# board.net
KiCad netlist of a schematic drawn in EAGLE
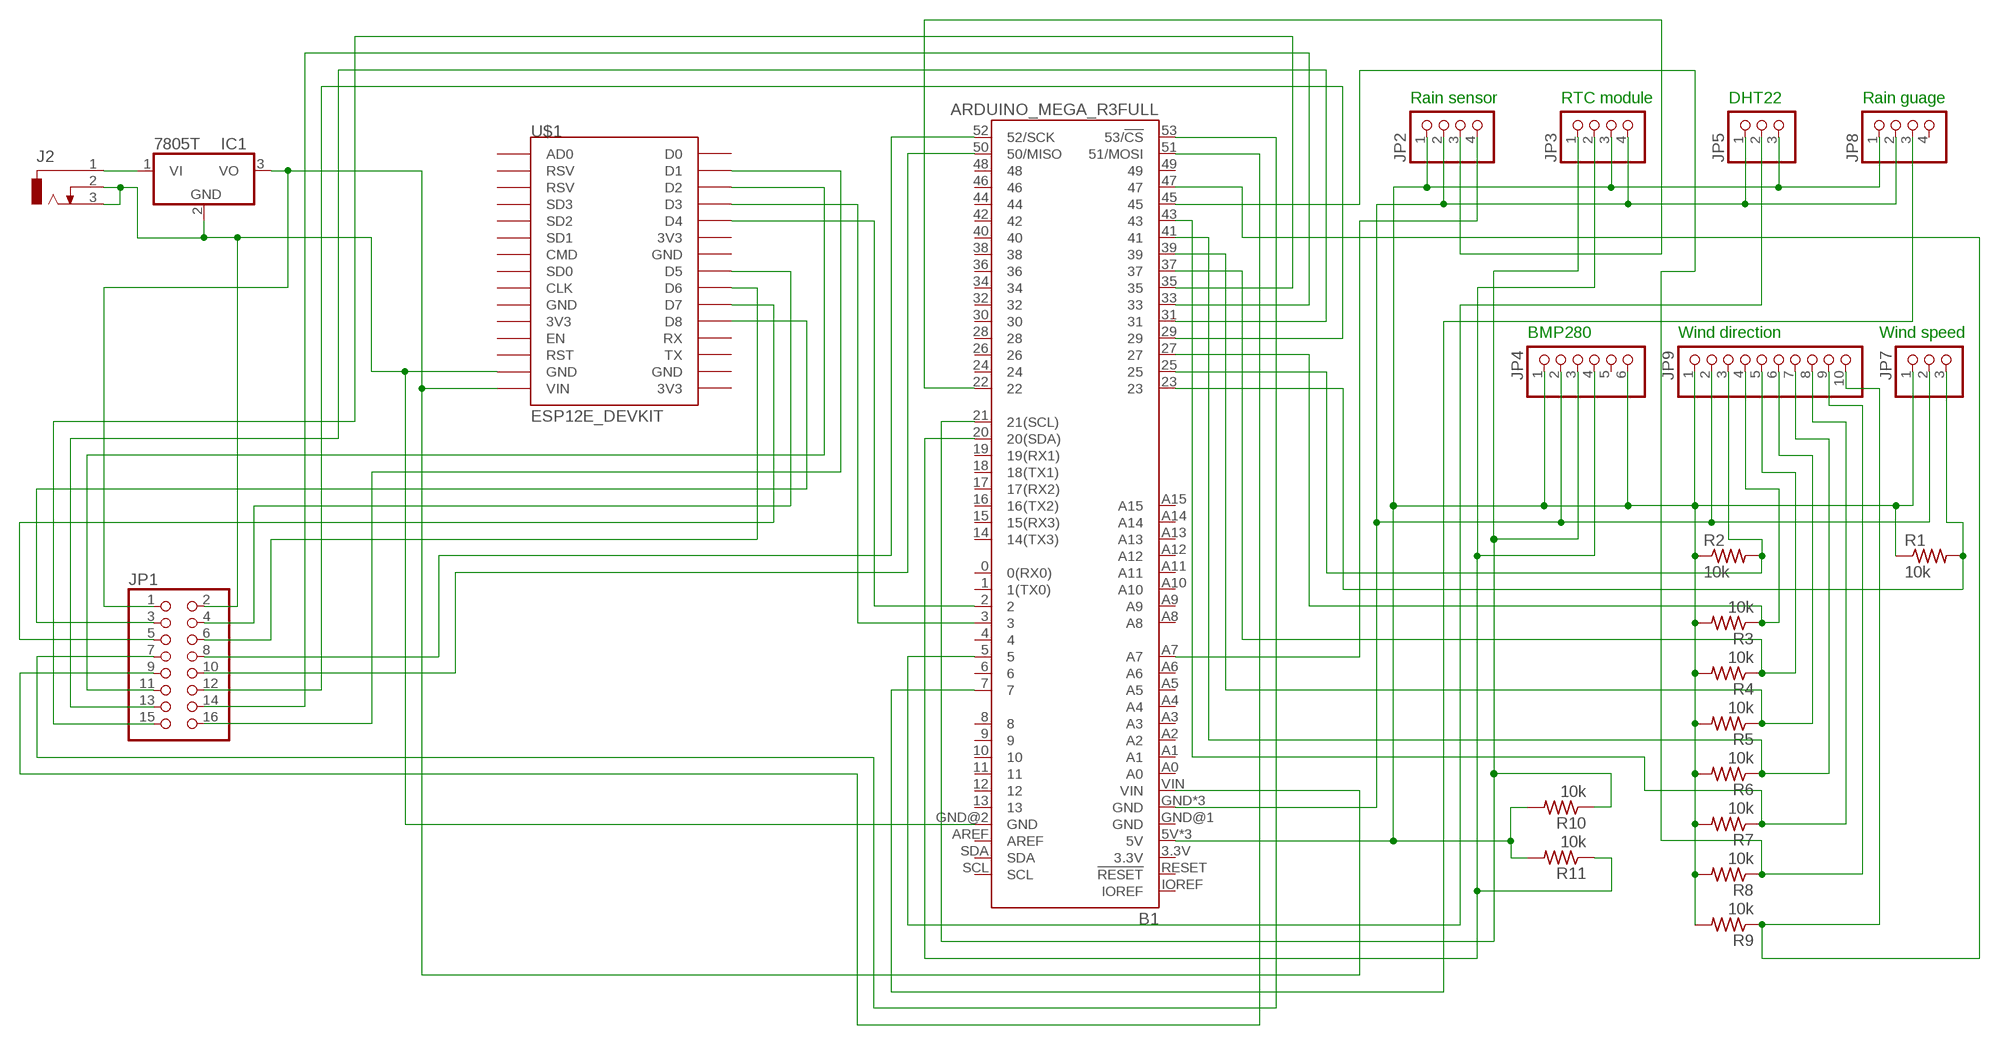
[diagram p0: schematic, sheet 1]

(export (version "E")
  (design (tool "Eeschema 10.0.6"))
  (components
    (comp (ref "B1")
      (value "ARDUINO_MEGA_R3FULL")
      (footprint "eagle-import:ARDUINO_MEGA_NO_SILK")
      (libsource (lib "eagle-import") (part "ARDUINO_MEGA_R3FULL"))
    )
    (comp (ref "IC1")
      (value "7805T")
      (footprint "eagle-import:TO220H")
      (libsource (lib "eagle-import") (part "78T05"))
    )
    (comp (ref "J2")
      (value "DCJ0303")
      (footprint "eagle-import:DCJ0303")
      (libsource (lib "eagle-import") (part "DCJ0303"))
    )
    (comp (ref "JP1")
      (value "PINHD-2X8/90")
      (footprint "eagle-import:2X08_90")
      (libsource (lib "eagle-import") (part "PINHD-2X8/90"))
    )
    (comp (ref "JP2")
      (value "PINHD-1X4")
      (footprint "eagle-import:1X04")
      (libsource (lib "eagle-import") (part "PINHD-1X4"))
    )
    (comp (ref "JP3")
      (value "PINHD-1X4")
      (footprint "eagle-import:1X04")
      (libsource (lib "eagle-import") (part "PINHD-1X4"))
    )
    (comp (ref "JP4")
      (value "PINHD-1X6")
      (footprint "eagle-import:1X06")
      (libsource (lib "eagle-import") (part "PINHD-1X6"))
    )
    (comp (ref "JP5")
      (value "PINHD-1X3")
      (footprint "eagle-import:1X03")
      (libsource (lib "eagle-import") (part "PINHD-1X3"))
    )
    (comp (ref "JP7")
      (value "PINHD-1X3")
      (footprint "eagle-import:1X03")
      (libsource (lib "eagle-import") (part "PINHD-1X3"))
    )
    (comp (ref "JP8")
      (value "PINHD-1X4")
      (footprint "eagle-import:1X04")
      (libsource (lib "eagle-import") (part "PINHD-1X4"))
    )
    (comp (ref "JP9")
      (value "PINHD-1X10")
      (footprint "eagle-import:1X10")
      (libsource (lib "eagle-import") (part "PINHD-1X10"))
    )
    (comp (ref "R1")
      (value "10k")
      (footprint "eagle-import:0207_10")
      (libsource (lib "eagle-import") (part "R-US_0207/10"))
    )
    (comp (ref "R2")
      (value "10k")
      (footprint "eagle-import:0207_10")
      (libsource (lib "eagle-import") (part "R-US_0207/10"))
    )
    (comp (ref "R3")
      (value "10k")
      (footprint "eagle-import:0207_10")
      (libsource (lib "eagle-import") (part "R-US_0207/10"))
    )
    (comp (ref "R4")
      (value "10k")
      (footprint "eagle-import:0207_10")
      (libsource (lib "eagle-import") (part "R-US_0207/10"))
    )
    (comp (ref "R5")
      (value "10k")
      (footprint "eagle-import:0207_10")
      (libsource (lib "eagle-import") (part "R-US_0207/10"))
    )
    (comp (ref "R6")
      (value "10k")
      (footprint "eagle-import:0207_10")
      (libsource (lib "eagle-import") (part "R-US_0207/10"))
    )
    (comp (ref "R7")
      (value "10k")
      (footprint "eagle-import:0207_10")
      (libsource (lib "eagle-import") (part "R-US_0207/10"))
    )
    (comp (ref "R8")
      (value "10k")
      (footprint "eagle-import:0207_10")
      (libsource (lib "eagle-import") (part "R-US_0207/10"))
    )
    (comp (ref "R9")
      (value "10k")
      (footprint "eagle-import:0207_10")
      (libsource (lib "eagle-import") (part "R-US_0207/10"))
    )
    (comp (ref "R10")
      (value "10k")
      (footprint "eagle-import:0207_10")
      (libsource (lib "eagle-import") (part "R-US_0207/10"))
    )
    (comp (ref "R11")
      (value "10k")
      (footprint "eagle-import:0207_10")
      (libsource (lib "eagle-import") (part "R-US_0207/10"))
    )
    (comp (ref "U$1")
      (value "ESP12E_DEVKIT")
      (footprint "eagle-import:ESP12E_DEVKIT")
      (libsource (lib "eagle-import") (part "ESP12E_DEVKIT"))
    )
  )
  (nets
    (net (code "1") (name "Net-(B1-5V-Pad5V@1)") (class "Default")
      (node (ref "B1") (pin "5V") (pinfunction "5V_5V") (pintype "bidirectional"))
      (node (ref "B1") (pin "5V@1") (pinfunction "5V_5V@1") (pintype "bidirectional"))
      (node (ref "B1") (pin "5V@2") (pinfunction "5V_5V@2") (pintype "bidirectional"))
      (node (ref "JP2") (pin "1") (pinfunction "1_1") (pintype "passive"))
      (node (ref "JP3") (pin "3") (pinfunction "3_3") (pintype "passive"))
      (node (ref "JP4") (pin "1") (pinfunction "1_1") (pintype "passive"))
      (node (ref "JP4") (pin "6") (pinfunction "6_6") (pintype "passive"))
      (node (ref "JP5") (pin "3") (pinfunction "3_3") (pintype "passive"))
      (node (ref "JP7") (pin "1") (pinfunction "1_1") (pintype "passive"))
      (node (ref "JP8") (pin "1") (pinfunction "1_1") (pintype "passive"))
      (node (ref "JP9") (pin "1") (pinfunction "1_1") (pintype "passive"))
      (node (ref "R1") (pin "1") (pinfunction "1_1") (pintype "passive"))
      (node (ref "R10") (pin "2") (pinfunction "2_2") (pintype "passive"))
      (node (ref "R11") (pin "2") (pinfunction "2_2") (pintype "passive"))
      (node (ref "R2") (pin "1") (pinfunction "1_1") (pintype "passive"))
      (node (ref "R3") (pin "2") (pinfunction "2_2") (pintype "passive"))
      (node (ref "R4") (pin "2") (pinfunction "2_2") (pintype "passive"))
      (node (ref "R5") (pin "2") (pinfunction "2_2") (pintype "passive"))
      (node (ref "R6") (pin "2") (pinfunction "2_2") (pintype "passive"))
      (node (ref "R7") (pin "2") (pinfunction "2_2") (pintype "passive"))
      (node (ref "R8") (pin "2") (pinfunction "2_2") (pintype "passive"))
      (node (ref "R9") (pin "2") (pinfunction "2_2") (pintype "passive"))
    )
    (net (code "2") (name "Net-(B1-20(SDA))") (class "Default")
      (node (ref "B1") (pin "20") (pinfunction "20(SDA)_20") (pintype "bidirectional"))
      (node (ref "JP3") (pin "2") (pinfunction "2_2") (pintype "passive"))
      (node (ref "JP4") (pin "4") (pinfunction "4_4") (pintype "passive"))
      (node (ref "R11") (pin "1") (pinfunction "1_1") (pintype "passive"))
    )
    (net (code "3") (name "Net-(B1-21(SCL))") (class "Default")
      (node (ref "B1") (pin "21") (pinfunction "21(SCL)_21") (pintype "bidirectional"))
      (node (ref "JP3") (pin "1") (pinfunction "1_1") (pintype "passive"))
      (node (ref "JP4") (pin "3") (pinfunction "3_3") (pintype "passive"))
      (node (ref "R10") (pin "1") (pinfunction "1_1") (pintype "passive"))
    )
    (net (code "4") (name "Net-(B1-50{slash}MISO)") (class "Default")
      (node (ref "B1") (pin "50") (pinfunction "50/MISO_50") (pintype "bidirectional"))
      (node (ref "JP1") (pin "10") (pinfunction "10_10") (pintype "passive"))
    )
    (net (code "5") (name "Net-(B1-51{slash}MOSI)") (class "Default")
      (node (ref "B1") (pin "51") (pinfunction "51/MOSI_51") (pintype "bidirectional"))
      (node (ref "JP1") (pin "9") (pinfunction "9_9") (pintype "passive"))
    )
    (net (code "6") (name "Net-(B1-52{slash}SCK)") (class "Default")
      (node (ref "B1") (pin "52") (pinfunction "52/SCK_52") (pintype "bidirectional"))
      (node (ref "JP1") (pin "8") (pinfunction "8_8") (pintype "passive"))
    )
    (net (code "7") (name "Net-(B1-53{slash}~{CS})") (class "Default")
      (node (ref "B1") (pin "53") (pinfunction "53/~{CS}_53") (pintype "bidirectional"))
      (node (ref "JP1") (pin "7") (pinfunction "7_7") (pintype "passive"))
    )
    (net (code "8") (name "Net-(B1-GND-PadGND@3)") (class "Default")
      (node (ref "B1") (pin "GND") (pinfunction "GND_GND") (pintype "bidirectional"))
      (node (ref "B1") (pin "GND@3") (pinfunction "GND_GND@3") (pintype "bidirectional"))
      (node (ref "B1") (pin "GND@4") (pinfunction "GND_GND@4") (pintype "bidirectional"))
      (node (ref "JP2") (pin "2") (pinfunction "2_2") (pintype "passive"))
      (node (ref "JP3") (pin "4") (pinfunction "4_4") (pintype "passive"))
      (node (ref "JP4") (pin "2") (pinfunction "2_2") (pintype "passive"))
      (node (ref "JP5") (pin "1") (pinfunction "1_1") (pintype "passive"))
      (node (ref "JP7") (pin "2") (pinfunction "2_2") (pintype "passive"))
      (node (ref "JP8") (pin "2") (pinfunction "2_2") (pintype "passive"))
      (node (ref "JP9") (pin "2") (pinfunction "2_2") (pintype "passive"))
    )
    (net (code "9") (name "Net-(B1-Pad2)") (class "Default")
      (node (ref "B1") (pin "2") (pinfunction "2_2") (pintype "bidirectional"))
      (node (ref "U$1") (pin "D4") (pinfunction "D4_D4") (pintype "bidirectional"))
    )
    (net (code "10") (name "Net-(B1-Pad3)") (class "Default")
      (node (ref "B1") (pin "3") (pinfunction "3_3") (pintype "bidirectional"))
      (node (ref "U$1") (pin "D3") (pinfunction "D3_D3") (pintype "bidirectional"))
    )
    (net (code "11") (name "Net-(B1-Pad5)") (class "Default")
      (node (ref "B1") (pin "5") (pinfunction "5_5") (pintype "bidirectional"))
      (node (ref "JP5") (pin "2") (pinfunction "2_2") (pintype "passive"))
    )
    (net (code "12") (name "Net-(B1-Pad7)") (class "Default")
      (node (ref "B1") (pin "7") (pinfunction "7_7") (pintype "bidirectional"))
      (node (ref "JP8") (pin "3") (pinfunction "3_3") (pintype "passive"))
    )
    (net (code "13") (name "Net-(B1-Pad22)") (class "Default")
      (node (ref "B1") (pin "22") (pinfunction "22_22") (pintype "bidirectional"))
      (node (ref "JP2") (pin "3") (pinfunction "3_3") (pintype "passive"))
    )
    (net (code "14") (name "Net-(B1-Pad23)") (class "Default")
      (node (ref "B1") (pin "23") (pinfunction "23_23") (pintype "bidirectional"))
      (node (ref "JP7") (pin "3") (pinfunction "3_3") (pintype "passive"))
      (node (ref "R1") (pin "2") (pinfunction "2_2") (pintype "passive"))
    )
    (net (code "15") (name "Net-(B1-Pad25)") (class "Default")
      (node (ref "B1") (pin "25") (pinfunction "25_25") (pintype "bidirectional"))
      (node (ref "JP9") (pin "3") (pinfunction "3_3") (pintype "passive"))
      (node (ref "R2") (pin "2") (pinfunction "2_2") (pintype "passive"))
    )
    (net (code "16") (name "Net-(B1-Pad27)") (class "Default")
      (node (ref "B1") (pin "27") (pinfunction "27_27") (pintype "bidirectional"))
      (node (ref "JP9") (pin "4") (pinfunction "4_4") (pintype "passive"))
      (node (ref "R3") (pin "1") (pinfunction "1_1") (pintype "passive"))
    )
    (net (code "17") (name "Net-(B1-Pad29)") (class "Default")
      (node (ref "B1") (pin "29") (pinfunction "29_29") (pintype "bidirectional"))
      (node (ref "JP1") (pin "12") (pinfunction "12_12") (pintype "passive"))
    )
    (net (code "18") (name "Net-(B1-Pad31)") (class "Default")
      (node (ref "B1") (pin "31") (pinfunction "31_31") (pintype "bidirectional"))
      (node (ref "JP1") (pin "13") (pinfunction "13_13") (pintype "passive"))
    )
    (net (code "19") (name "Net-(B1-Pad33)") (class "Default")
      (node (ref "B1") (pin "33") (pinfunction "33_33") (pintype "bidirectional"))
      (node (ref "JP1") (pin "14") (pinfunction "14_14") (pintype "passive"))
    )
    (net (code "20") (name "Net-(B1-Pad35)") (class "Default")
      (node (ref "B1") (pin "35") (pinfunction "35_35") (pintype "bidirectional"))
      (node (ref "JP1") (pin "15") (pinfunction "15_15") (pintype "passive"))
    )
    (net (code "21") (name "Net-(B1-Pad37)") (class "Default")
      (node (ref "B1") (pin "37") (pinfunction "37_37") (pintype "bidirectional"))
      (node (ref "JP9") (pin "5") (pinfunction "5_5") (pintype "passive"))
      (node (ref "R4") (pin "1") (pinfunction "1_1") (pintype "passive"))
    )
    (net (code "22") (name "Net-(B1-Pad39)") (class "Default")
      (node (ref "B1") (pin "39") (pinfunction "39_39") (pintype "bidirectional"))
      (node (ref "JP9") (pin "6") (pinfunction "6_6") (pintype "passive"))
      (node (ref "R5") (pin "1") (pinfunction "1_1") (pintype "passive"))
    )
    (net (code "23") (name "Net-(B1-Pad41)") (class "Default")
      (node (ref "B1") (pin "41") (pinfunction "41_41") (pintype "bidirectional"))
      (node (ref "JP9") (pin "7") (pinfunction "7_7") (pintype "passive"))
      (node (ref "R6") (pin "1") (pinfunction "1_1") (pintype "passive"))
    )
    (net (code "24") (name "Net-(B1-Pad43)") (class "Default")
      (node (ref "B1") (pin "43") (pinfunction "43_43") (pintype "bidirectional"))
      (node (ref "JP9") (pin "8") (pinfunction "8_8") (pintype "passive"))
      (node (ref "R7") (pin "1") (pinfunction "1_1") (pintype "passive"))
    )
    (net (code "25") (name "Net-(B1-Pad45)") (class "Default")
      (node (ref "B1") (pin "45") (pinfunction "45_45") (pintype "bidirectional"))
      (node (ref "JP9") (pin "9") (pinfunction "9_9") (pintype "passive"))
      (node (ref "R8") (pin "1") (pinfunction "1_1") (pintype "passive"))
    )
    (net (code "26") (name "Net-(B1-Pad47)") (class "Default")
      (node (ref "B1") (pin "47") (pinfunction "47_47") (pintype "bidirectional"))
      (node (ref "JP9") (pin "10") (pinfunction "10_10") (pintype "passive"))
      (node (ref "R9") (pin "1") (pinfunction "1_1") (pintype "passive"))
    )
    (net (code "27") (name "Net-(B1-PadA7)") (class "Default")
      (node (ref "B1") (pin "A7") (pinfunction "A7_A7") (pintype "bidirectional"))
      (node (ref "JP2") (pin "4") (pinfunction "4_4") (pintype "passive"))
    )
    (net (code "28") (name "Net-(IC1-GND)") (class "Default")
      (node (ref "B1") (pin "GND@2") (pinfunction "GND_GND@2") (pintype "bidirectional"))
      (node (ref "IC1") (pin "2") (pinfunction "GND_2") (pintype "passive"))
      (node (ref "J2") (pin "2") (pinfunction "2_2") (pintype "passive"))
      (node (ref "J2") (pin "3") (pinfunction "3_3") (pintype "passive"))
      (node (ref "JP1") (pin "2") (pinfunction "2_2") (pintype "passive"))
      (node (ref "U$1") (pin "GND@1") (pinfunction "GND_GND@1") (pintype "bidirectional"))
    )
    (net (code "29") (name "Net-(IC1-VI)") (class "Default")
      (node (ref "IC1") (pin "1") (pinfunction "VI_1") (pintype "input"))
      (node (ref "J2") (pin "1") (pinfunction "1_1") (pintype "passive"))
    )
    (net (code "30") (name "Net-(IC1-VO)") (class "Default")
      (node (ref "B1") (pin "VIN") (pinfunction "VIN_VIN") (pintype "bidirectional"))
      (node (ref "IC1") (pin "3") (pinfunction "VO_3") (pintype "passive"))
      (node (ref "JP1") (pin "1") (pinfunction "1_1") (pintype "passive"))
      (node (ref "U$1") (pin "VIN") (pinfunction "VIN_VIN") (pintype "bidirectional"))
    )
    (net (code "31") (name "Net-(JP1-Pad3)") (class "Default")
      (node (ref "JP1") (pin "3") (pinfunction "3_3") (pintype "passive"))
      (node (ref "U$1") (pin "D8") (pinfunction "D8_D8") (pintype "bidirectional"))
    )
    (net (code "32") (name "Net-(JP1-Pad4)") (class "Default")
      (node (ref "JP1") (pin "4") (pinfunction "4_4") (pintype "passive"))
      (node (ref "U$1") (pin "D5") (pinfunction "D5_D5") (pintype "bidirectional"))
    )
    (net (code "33") (name "Net-(JP1-Pad5)") (class "Default")
      (node (ref "JP1") (pin "5") (pinfunction "5_5") (pintype "passive"))
      (node (ref "U$1") (pin "D7") (pinfunction "D7_D7") (pintype "bidirectional"))
    )
    (net (code "34") (name "Net-(JP1-Pad6)") (class "Default")
      (node (ref "JP1") (pin "6") (pinfunction "6_6") (pintype "passive"))
      (node (ref "U$1") (pin "D6") (pinfunction "D6_D6") (pintype "bidirectional"))
    )
    (net (code "35") (name "Net-(JP1-Pad11)") (class "Default")
      (node (ref "JP1") (pin "11") (pinfunction "11_11") (pintype "passive"))
      (node (ref "U$1") (pin "D2") (pinfunction "D2_D2") (pintype "bidirectional"))
    )
    (net (code "36") (name "Net-(JP1-Pad16)") (class "Default")
      (node (ref "JP1") (pin "16") (pinfunction "16_16") (pintype "passive"))
      (node (ref "U$1") (pin "D1") (pinfunction "D1_D1") (pintype "bidirectional"))
    )
    (net (code "37") (name "unconnected-(B1-0(RX0)-Pad0)") (class "Default")
      (node (ref "B1") (pin "0") (pinfunction "0(RX0)_0") (pintype "bidirectional"))
    )
    (net (code "38") (name "unconnected-(B1-1(TX0)-Pad1)") (class "Default")
      (node (ref "B1") (pin "1") (pinfunction "1(TX0)_1") (pintype "bidirectional"))
    )
    (net (code "39") (name "unconnected-(B1-14(TX3)-Pad14)") (class "Default")
      (node (ref "B1") (pin "14") (pinfunction "14(TX3)_14") (pintype "bidirectional"))
    )
    (net (code "40") (name "unconnected-(B1-15(RX3)-Pad15)") (class "Default")
      (node (ref "B1") (pin "15") (pinfunction "15(RX3)_15") (pintype "bidirectional"))
    )
    (net (code "41") (name "unconnected-(B1-16(TX2)-Pad16)") (class "Default")
      (node (ref "B1") (pin "16") (pinfunction "16(TX2)_16") (pintype "bidirectional"))
    )
    (net (code "42") (name "unconnected-(B1-17(RX2)-Pad17)") (class "Default")
      (node (ref "B1") (pin "17") (pinfunction "17(RX2)_17") (pintype "bidirectional"))
    )
    (net (code "43") (name "unconnected-(B1-18(TX1)-Pad18)") (class "Default")
      (node (ref "B1") (pin "18") (pinfunction "18(TX1)_18") (pintype "bidirectional"))
    )
    (net (code "44") (name "unconnected-(B1-19(RX1)-Pad19)") (class "Default")
      (node (ref "B1") (pin "19") (pinfunction "19(RX1)_19") (pintype "bidirectional"))
    )
    (net (code "45") (name "unconnected-(B1-GND-PadGND@1)") (class "Default")
      (node (ref "B1") (pin "GND@1") (pinfunction "GND_GND@1") (pintype "bidirectional"))
    )
    (net (code "46") (name "unconnected-(B1-Pad3.3V)") (class "Default")
      (node (ref "B1") (pin "3.3V") (pinfunction "3.3V_3.3V") (pintype "bidirectional"))
    )
    (net (code "47") (name "unconnected-(B1-Pad4)") (class "Default")
      (node (ref "B1") (pin "4") (pinfunction "4_4") (pintype "bidirectional"))
    )
    (net (code "48") (name "unconnected-(B1-Pad6)") (class "Default")
      (node (ref "B1") (pin "6") (pinfunction "6_6") (pintype "bidirectional"))
    )
    (net (code "49") (name "unconnected-(B1-Pad8)") (class "Default")
      (node (ref "B1") (pin "8") (pinfunction "8_8") (pintype "bidirectional"))
    )
    (net (code "50") (name "unconnected-(B1-Pad9)") (class "Default")
      (node (ref "B1") (pin "9") (pinfunction "9_9") (pintype "bidirectional"))
    )
    (net (code "51") (name "unconnected-(B1-Pad10)") (class "Default")
      (node (ref "B1") (pin "10") (pinfunction "10_10") (pintype "bidirectional"))
    )
    (net (code "52") (name "unconnected-(B1-Pad11)") (class "Default")
      (node (ref "B1") (pin "11") (pinfunction "11_11") (pintype "bidirectional"))
    )
    (net (code "53") (name "unconnected-(B1-Pad12)") (class "Default")
      (node (ref "B1") (pin "12") (pinfunction "12_12") (pintype "bidirectional"))
    )
    (net (code "54") (name "unconnected-(B1-Pad13)") (class "Default")
      (node (ref "B1") (pin "13") (pinfunction "13_13") (pintype "bidirectional"))
    )
    (net (code "55") (name "unconnected-(B1-Pad24)") (class "Default")
      (node (ref "B1") (pin "24") (pinfunction "24_24") (pintype "bidirectional"))
    )
    (net (code "56") (name "unconnected-(B1-Pad26)") (class "Default")
      (node (ref "B1") (pin "26") (pinfunction "26_26") (pintype "bidirectional"))
    )
    (net (code "57") (name "unconnected-(B1-Pad28)") (class "Default")
      (node (ref "B1") (pin "28") (pinfunction "28_28") (pintype "bidirectional"))
    )
    (net (code "58") (name "unconnected-(B1-Pad30)") (class "Default")
      (node (ref "B1") (pin "30") (pinfunction "30_30") (pintype "bidirectional"))
    )
    (net (code "59") (name "unconnected-(B1-Pad32)") (class "Default")
      (node (ref "B1") (pin "32") (pinfunction "32_32") (pintype "bidirectional"))
    )
    (net (code "60") (name "unconnected-(B1-Pad34)") (class "Default")
      (node (ref "B1") (pin "34") (pinfunction "34_34") (pintype "bidirectional"))
    )
    (net (code "61") (name "unconnected-(B1-Pad36)") (class "Default")
      (node (ref "B1") (pin "36") (pinfunction "36_36") (pintype "bidirectional"))
    )
    (net (code "62") (name "unconnected-(B1-Pad38)") (class "Default")
      (node (ref "B1") (pin "38") (pinfunction "38_38") (pintype "bidirectional"))
    )
    (net (code "63") (name "unconnected-(B1-Pad40)") (class "Default")
      (node (ref "B1") (pin "40") (pinfunction "40_40") (pintype "bidirectional"))
    )
    (net (code "64") (name "unconnected-(B1-Pad42)") (class "Default")
      (node (ref "B1") (pin "42") (pinfunction "42_42") (pintype "bidirectional"))
    )
    (net (code "65") (name "unconnected-(B1-Pad44)") (class "Default")
      (node (ref "B1") (pin "44") (pinfunction "44_44") (pintype "bidirectional"))
    )
    (net (code "66") (name "unconnected-(B1-Pad46)") (class "Default")
      (node (ref "B1") (pin "46") (pinfunction "46_46") (pintype "bidirectional"))
    )
    (net (code "67") (name "unconnected-(B1-Pad48)") (class "Default")
      (node (ref "B1") (pin "48") (pinfunction "48_48") (pintype "bidirectional"))
    )
    (net (code "68") (name "unconnected-(B1-Pad49)") (class "Default")
      (node (ref "B1") (pin "49") (pinfunction "49_49") (pintype "bidirectional"))
    )
    (net (code "69") (name "unconnected-(B1-PadA0)") (class "Default")
      (node (ref "B1") (pin "A0") (pinfunction "A0_A0") (pintype "bidirectional"))
    )
    (net (code "70") (name "unconnected-(B1-PadA1)") (class "Default")
      (node (ref "B1") (pin "A1") (pinfunction "A1_A1") (pintype "bidirectional"))
    )
    (net (code "71") (name "unconnected-(B1-PadA2)") (class "Default")
      (node (ref "B1") (pin "A2") (pinfunction "A2_A2") (pintype "bidirectional"))
    )
    (net (code "72") (name "unconnected-(B1-PadA3)") (class "Default")
      (node (ref "B1") (pin "A3") (pinfunction "A3_A3") (pintype "bidirectional"))
    )
    (net (code "73") (name "unconnected-(B1-PadA4)") (class "Default")
      (node (ref "B1") (pin "A4") (pinfunction "A4_A4") (pintype "bidirectional"))
    )
    (net (code "74") (name "unconnected-(B1-PadA5)") (class "Default")
      (node (ref "B1") (pin "A5") (pinfunction "A5_A5") (pintype "bidirectional"))
    )
    (net (code "75") (name "unconnected-(B1-PadA6)") (class "Default")
      (node (ref "B1") (pin "A6") (pinfunction "A6_A6") (pintype "bidirectional"))
    )
    (net (code "76") (name "unconnected-(B1-PadA8)") (class "Default")
      (node (ref "B1") (pin "A8") (pinfunction "A8_A8") (pintype "bidirectional"))
    )
    (net (code "77") (name "unconnected-(B1-PadA9)") (class "Default")
      (node (ref "B1") (pin "A9") (pinfunction "A9_A9") (pintype "bidirectional"))
    )
    (net (code "78") (name "unconnected-(B1-PadA10)") (class "Default")
      (node (ref "B1") (pin "A10") (pinfunction "A10_A10") (pintype "bidirectional"))
    )
    (net (code "79") (name "unconnected-(B1-PadA11)") (class "Default")
      (node (ref "B1") (pin "A11") (pinfunction "A11_A11") (pintype "bidirectional"))
    )
    (net (code "80") (name "unconnected-(B1-PadA12)") (class "Default")
      (node (ref "B1") (pin "A12") (pinfunction "A12_A12") (pintype "bidirectional"))
    )
    (net (code "81") (name "unconnected-(B1-PadA13)") (class "Default")
      (node (ref "B1") (pin "A13") (pinfunction "A13_A13") (pintype "bidirectional"))
    )
    (net (code "82") (name "unconnected-(B1-PadA14)") (class "Default")
      (node (ref "B1") (pin "A14") (pinfunction "A14_A14") (pintype "bidirectional"))
    )
    (net (code "83") (name "unconnected-(B1-PadA15)") (class "Default")
      (node (ref "B1") (pin "A15") (pinfunction "A15_A15") (pintype "bidirectional"))
    )
    (net (code "84") (name "unconnected-(B1-PadAREF)") (class "Default")
      (node (ref "B1") (pin "AREF") (pinfunction "AREF_AREF") (pintype "bidirectional"))
    )
    (net (code "85") (name "unconnected-(B1-PadIOREF)") (class "Default")
      (node (ref "B1") (pin "IOREF") (pinfunction "IOREF_IOREF") (pintype "bidirectional"))
    )
    (net (code "86") (name "unconnected-(B1-PadSCL)") (class "Default")
      (node (ref "B1") (pin "SCL") (pinfunction "SCL_SCL") (pintype "bidirectional"))
    )
    (net (code "87") (name "unconnected-(B1-PadSDA)") (class "Default")
      (node (ref "B1") (pin "SDA") (pinfunction "SDA_SDA") (pintype "bidirectional"))
    )
    (net (code "88") (name "unconnected-(B1-~{RESET}-PadRESET)") (class "Default")
      (node (ref "B1") (pin "RESET") (pinfunction "~{RESET}_RESET") (pintype "bidirectional"))
    )
    (net (code "89") (name "unconnected-(JP4-Pad5)") (class "Default")
      (node (ref "JP4") (pin "5") (pinfunction "5_5") (pintype "passive"))
    )
    (net (code "90") (name "unconnected-(JP8-Pad4)") (class "Default")
      (node (ref "JP8") (pin "4") (pinfunction "4_4") (pintype "passive"))
    )
    (net (code "91") (name "unconnected-(U$1-3V3-Pad3V3@0)") (class "Default")
      (node (ref "U$1") (pin "3V3@0") (pinfunction "3V3_3V3@0") (pintype "bidirectional"))
    )
    (net (code "92") (name "unconnected-(U$1-3V3-Pad3V3@1)") (class "Default")
      (node (ref "U$1") (pin "3V3@1") (pinfunction "3V3_3V3@1") (pintype "bidirectional"))
    )
    (net (code "93") (name "unconnected-(U$1-3V3-Pad3V3@2)") (class "Default")
      (node (ref "U$1") (pin "3V3@2") (pinfunction "3V3_3V3@2") (pintype "bidirectional"))
    )
    (net (code "94") (name "unconnected-(U$1-GND-PadGND@0)") (class "Default")
      (node (ref "U$1") (pin "GND@0") (pinfunction "GND_GND@0") (pintype "bidirectional"))
    )
    (net (code "95") (name "unconnected-(U$1-GND-PadGND@2)") (class "Default")
      (node (ref "U$1") (pin "GND@2") (pinfunction "GND_GND@2") (pintype "bidirectional"))
    )
    (net (code "96") (name "unconnected-(U$1-GND-PadGND@3)") (class "Default")
      (node (ref "U$1") (pin "GND@3") (pinfunction "GND_GND@3") (pintype "bidirectional"))
    )
    (net (code "97") (name "unconnected-(U$1-PadAD0)") (class "Default")
      (node (ref "U$1") (pin "AD0") (pinfunction "AD0_AD0") (pintype "bidirectional"))
    )
    (net (code "98") (name "unconnected-(U$1-PadCLK)") (class "Default")
      (node (ref "U$1") (pin "CLK") (pinfunction "CLK_CLK") (pintype "bidirectional"))
    )
    (net (code "99") (name "unconnected-(U$1-PadCMD)") (class "Default")
      (node (ref "U$1") (pin "CMD") (pinfunction "CMD_CMD") (pintype "bidirectional"))
    )
    (net (code "100") (name "unconnected-(U$1-PadD0)") (class "Default")
      (node (ref "U$1") (pin "D0") (pinfunction "D0_D0") (pintype "bidirectional"))
    )
    (net (code "101") (name "unconnected-(U$1-PadEN)") (class "Default")
      (node (ref "U$1") (pin "EN") (pinfunction "EN_EN") (pintype "bidirectional"))
    )
    (net (code "102") (name "unconnected-(U$1-PadRST)") (class "Default")
      (node (ref "U$1") (pin "RST") (pinfunction "RST_RST") (pintype "bidirectional"))
    )
    (net (code "103") (name "unconnected-(U$1-PadRX)") (class "Default")
      (node (ref "U$1") (pin "RX") (pinfunction "RX_RX") (pintype "bidirectional"))
    )
    (net (code "104") (name "unconnected-(U$1-PadSD0)") (class "Default")
      (node (ref "U$1") (pin "SD0") (pinfunction "SD0_SD0") (pintype "bidirectional"))
    )
    (net (code "105") (name "unconnected-(U$1-PadSD1)") (class "Default")
      (node (ref "U$1") (pin "SD1") (pinfunction "SD1_SD1") (pintype "bidirectional"))
    )
    (net (code "106") (name "unconnected-(U$1-PadSD2)") (class "Default")
      (node (ref "U$1") (pin "SD2") (pinfunction "SD2_SD2") (pintype "bidirectional"))
    )
    (net (code "107") (name "unconnected-(U$1-PadSD3)") (class "Default")
      (node (ref "U$1") (pin "SD3") (pinfunction "SD3_SD3") (pintype "bidirectional"))
    )
    (net (code "108") (name "unconnected-(U$1-PadTX)") (class "Default")
      (node (ref "U$1") (pin "TX") (pinfunction "TX_TX") (pintype "bidirectional"))
    )
    (net (code "109") (name "unconnected-(U$1-RSV-PadRSV@0)") (class "Default")
      (node (ref "U$1") (pin "RSV@0") (pinfunction "RSV_RSV@0") (pintype "bidirectional"))
    )
    (net (code "110") (name "unconnected-(U$1-RSV-PadRSV@1)") (class "Default")
      (node (ref "U$1") (pin "RSV@1") (pinfunction "RSV_RSV@1") (pintype "bidirectional"))
    )
  )
)
